# 0.net
KiCad netlist of a schematic drawn in Altium Designer
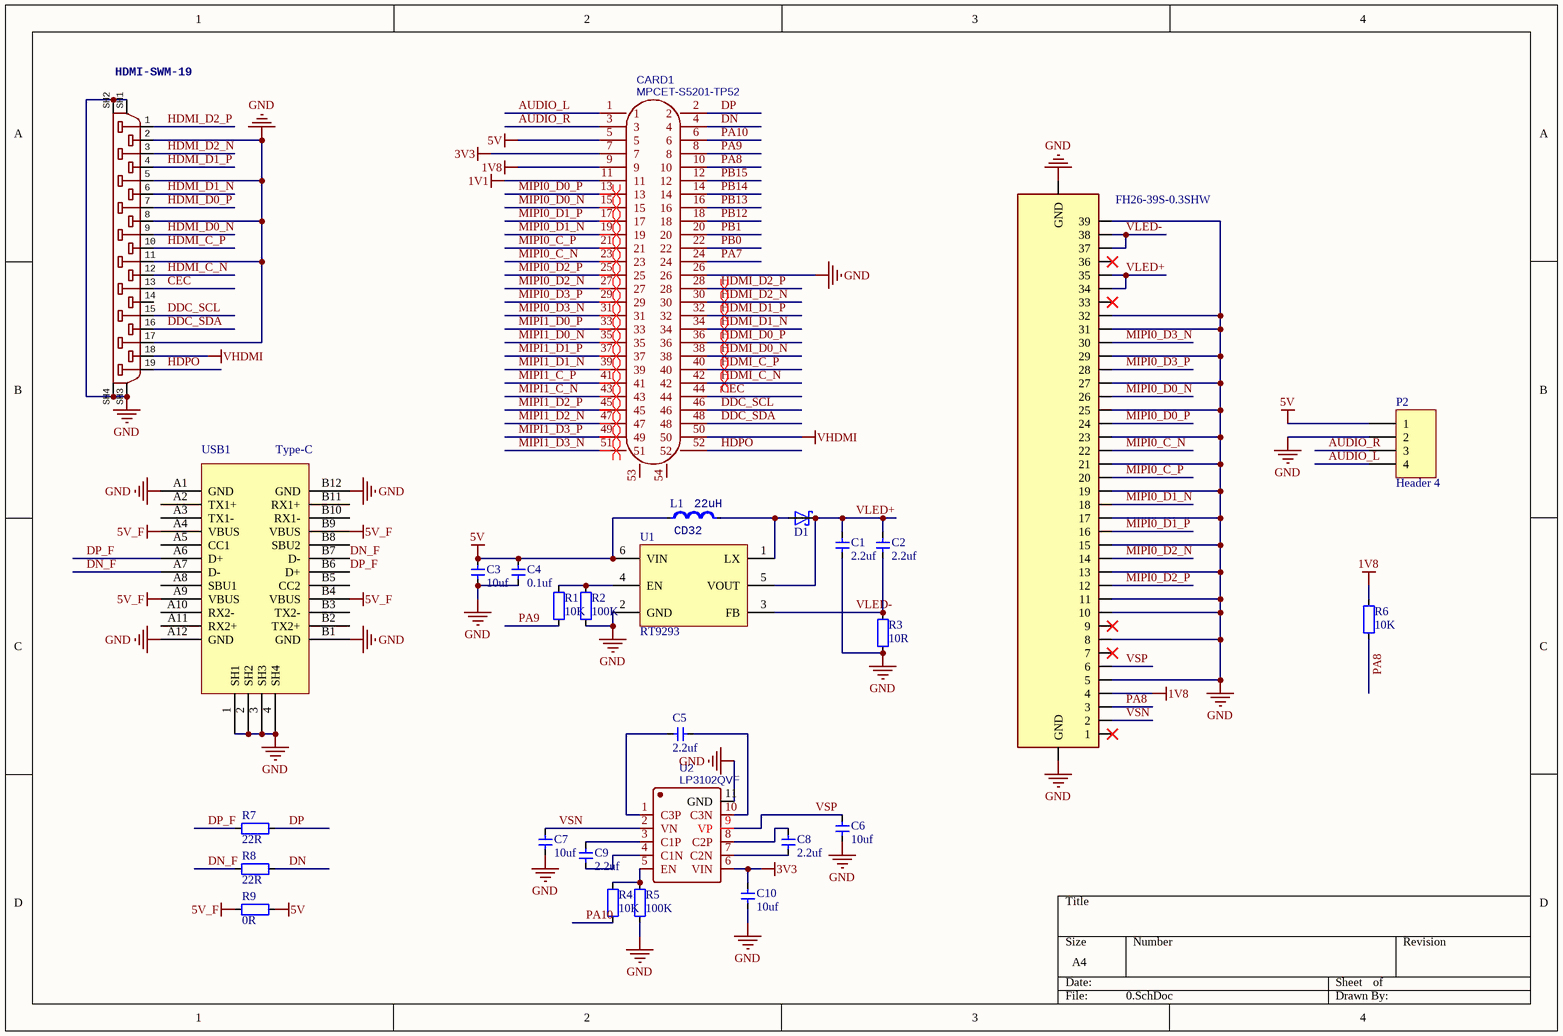
[diagram p0: 0.SchDoc]

(export (version "E")
  (design (tool "Eeschema 10.0.6"))
  (components
    (comp (ref "1")
      (value "FH26-39S-0.3SHW")
      (footprint "FH26-39S-0.3SHW")
      (description "39 Position FPC Connector Contacts, Bottom 0.012 _0.30mm_ Surface Mount, Right Angle")
      (fields (field (name "MF") "Hirose"))
      (libsource (lib "mLib") (part "FH26-39S-0.3SHW"))
    )
    (comp (ref "C1")
      (value "2.2uf")
      (footprint "0603_CAP")
      (description "Capacitor")
      (libsource (lib "MyPcbLib") (part "电容-0402"))
    )
    (comp (ref "C2")
      (value "2.2uf")
      (footprint "0603_CAP")
      (description "Capacitor")
      (libsource (lib "MyPcbLib") (part "电容-0402"))
    )
    (comp (ref "C3")
      (value "10uf")
      (footprint "0603_CAP")
      (description "Capacitor")
      (libsource (lib "MyPcbLib") (part "电容-0402"))
    )
    (comp (ref "C4")
      (value "0.1uf")
      (footprint "0603_CAP")
      (description "Capacitor")
      (libsource (lib "MyPcbLib") (part "电容-0402"))
    )
    (comp (ref "C5")
      (value "2.2uf")
      (footprint "0603_CAP")
      (description "Capacitor")
      (libsource (lib "MyPcbLib") (part "电容-0402"))
    )
    (comp (ref "C6")
      (value "10uf")
      (footprint "0603_CAP")
      (description "Capacitor")
      (libsource (lib "MyPcbLib") (part "电容-0402"))
    )
    (comp (ref "C7")
      (value "10uf")
      (footprint "0603_CAP")
      (description "Capacitor")
      (libsource (lib "MyPcbLib") (part "电容-0402"))
    )
    (comp (ref "C8")
      (value "2.2uf")
      (footprint "0603_CAP")
      (description "Capacitor")
      (libsource (lib "MyPcbLib") (part "电容-0402"))
    )
    (comp (ref "C9")
      (value "2.2uf")
      (footprint "0603_CAP")
      (description "Capacitor")
      (libsource (lib "MyPcbLib") (part "电容-0402"))
    )
    (comp (ref "C10")
      (value "10uf")
      (footprint "0603_CAP")
      (description "Capacitor")
      (libsource (lib "MyPcbLib") (part "电容-0402"))
    )
    (comp (ref "CARD1")
      (value "MPCET-S5201-TP52")
      (footprint "MINI-PCIE-SMD_MPCET-S5201-TP40")
      (fields (field (name "BOM_SUPPLIER PART") "C367018") (field (name "CONTRIBUTOR") "LCSC"))
      (libsource (lib "altium-import") (part "root_0_MPCET-S5201-TP52_"))
    )
    (comp (ref "D1")
      (value "RSX501L-20")
      (footprint "SOD-123F_L2.8-W1.8-LS3.7-RD")
      (description "Diode Schottky 40V 1A Surface Mount SMA _DO-214AC_")
      (fields (field (name "MP") "SS14") (field (name "MF") "ON Semiconductor"))
      (libsource (lib "mLib") (part "RSX501L-20"))
    )
    (comp (ref "HDMI")
      (value "HDMI-SWM-19")
      (footprint "HDMI-SWM-19")
      (libsource (lib "mLib") (part "HDMI-MC34931HDMI-SWM-19"))
    )
    (comp (ref "L1")
      (value "22uH")
      (footprint "IND_CD32")
      (description "Inductor")
      (fields (field (name "TYPE") "CD32") (field (name "Comment") "CD32"))
      (libsource (lib "KitSprout") (part "Ind_CD32"))
    )
    (comp (ref "P2")
      (value "Header 4")
      (footprint "HDR1X4")
      (description "Header, 4-Pin")
      (fields (field (name "PUBLISHER") "Altium Limited"))
      (libsource (lib "Miscellaneous Connectors") (part "Header 4"))
    )
    (comp (ref "R1")
      (value "10K")
      (footprint "0603_RES")
      (description "Resistor")
      (libsource (lib "MyPcbLib") (part "电阻-0402"))
    )
    (comp (ref "R2")
      (value "100K")
      (footprint "0603_RES")
      (description "Resistor")
      (libsource (lib "MyPcbLib") (part "电阻-0402"))
    )
    (comp (ref "R3")
      (value "10R")
      (footprint "0603_RES")
      (description "Resistor")
      (libsource (lib "MyPcbLib") (part "电阻-0402"))
    )
    (comp (ref "R4")
      (value "10K")
      (footprint "0603_RES")
      (description "Resistor")
      (libsource (lib "MyPcbLib") (part "电阻-0402"))
    )
    (comp (ref "R5")
      (value "100K")
      (footprint "0603_RES")
      (description "Resistor")
      (libsource (lib "MyPcbLib") (part "电阻-0402"))
    )
    (comp (ref "R6")
      (value "10K")
      (footprint "0603_RES")
      (description "Resistor")
      (libsource (lib "MyPcbLib") (part "电阻-0402"))
    )
    (comp (ref "R7")
      (value "22R")
      (footprint "0603_RES")
      (description "Resistor")
      (libsource (lib "") (part "电阻-0402_1"))
    )
    (comp (ref "R8")
      (value "22R")
      (footprint "0603_RES")
      (description "Resistor")
      (libsource (lib "") (part "电阻-0402_1"))
    )
    (comp (ref "R9")
      (value "0R")
      (footprint "0603_RES")
      (description "Resistor")
      (libsource (lib "") (part "电阻-0402_1"))
    )
    (comp (ref "U1")
      (value "RT9293")
      (footprint "SOT23-6")
      (description "LCD-LED Driver")
      (libsource (lib "mLib") (part "RT9293"))
    )
    (comp (ref "U2")
      (value "LP3102QVF")
      (footprint "TDFN-10_L3.0-W3.0-P0.50-BL-EP")
      (fields (field (name "BOM_SUPPLIER PART") "C517005") (field (name "CONTRIBUTOR") "LCSC"))
      (libsource (lib "altium-import") (part "root_0_LP3102QVF_"))
    )
    (comp (ref "USB1")
      (value "Type-C")
      (footprint "Type-C-TOP")
      (libsource (lib "MyPcbLib") (part "USB-Type-C-TOP"))
    )
  )
  (nets
    (net (code "1") (name "/AUDIO_L") (class "Default")
      (node (ref "CARD1") (pin "1") (pinfunction "1_1") (pintype "passive"))
      (node (ref "P2") (pin "4") (pinfunction "4_4") (pintype "passive"))
    )
    (net (code "2") (name "/AUDIO_R") (class "Default")
      (node (ref "CARD1") (pin "3") (pinfunction "3_3") (pintype "passive"))
      (node (ref "P2") (pin "3") (pinfunction "3_3") (pintype "passive"))
    )
    (net (code "3") (name "/CEC") (class "Default")
      (node (ref "CARD1") (pin "44") (pinfunction "44_44") (pintype "passive"))
      (node (ref "HDMI") (pin "13") (pinfunction "13_13") (pintype "passive"))
    )
    (net (code "4") (name "/DDC_SCL") (class "Default")
      (node (ref "CARD1") (pin "46") (pinfunction "46_46") (pintype "passive"))
      (node (ref "HDMI") (pin "15") (pinfunction "15_15") (pintype "passive"))
    )
    (net (code "5") (name "/DDC_SDA") (class "Default")
      (node (ref "CARD1") (pin "48") (pinfunction "48_48") (pintype "passive"))
      (node (ref "HDMI") (pin "16") (pinfunction "16_16") (pintype "passive"))
    )
    (net (code "6") (name "/DN") (class "Default")
      (node (ref "CARD1") (pin "4") (pinfunction "4_4") (pintype "passive"))
      (node (ref "R8") (pin "2") (pinfunction "2_2") (pintype "passive"))
    )
    (net (code "7") (name "/DN_F") (class "Default")
      (node (ref "R8") (pin "1") (pinfunction "1_1") (pintype "passive"))
      (node (ref "USB1") (pin "A7") (pinfunction "D-_A7") (pintype "passive"))
      (node (ref "USB1") (pin "B7") (pinfunction "D-_B7") (pintype "passive"))
    )
    (net (code "8") (name "/DP") (class "Default")
      (node (ref "CARD1") (pin "2") (pinfunction "2_2") (pintype "passive"))
      (node (ref "R7") (pin "2") (pinfunction "2_2") (pintype "passive"))
    )
    (net (code "9") (name "/DP_F") (class "Default")
      (node (ref "R7") (pin "1") (pinfunction "1_1") (pintype "passive"))
      (node (ref "USB1") (pin "A6") (pinfunction "D+_A6") (pintype "passive"))
      (node (ref "USB1") (pin "B6") (pinfunction "D+_B6") (pintype "passive"))
    )
    (net (code "10") (name "/HDMI_C_N") (class "Default")
      (node (ref "CARD1") (pin "42") (pinfunction "42_42") (pintype "passive"))
      (node (ref "HDMI") (pin "12") (pinfunction "12_12") (pintype "passive"))
    )
    (net (code "11") (name "/HDMI_C_P") (class "Default")
      (node (ref "CARD1") (pin "40") (pinfunction "40_40") (pintype "passive"))
      (node (ref "HDMI") (pin "10") (pinfunction "10_10") (pintype "passive"))
    )
    (net (code "12") (name "/HDMI_D0_N") (class "Default")
      (node (ref "CARD1") (pin "38") (pinfunction "38_38") (pintype "passive"))
      (node (ref "HDMI") (pin "9") (pinfunction "9_9") (pintype "passive"))
    )
    (net (code "13") (name "/HDMI_D0_P") (class "Default")
      (node (ref "CARD1") (pin "36") (pinfunction "36_36") (pintype "passive"))
      (node (ref "HDMI") (pin "7") (pinfunction "7_7") (pintype "passive"))
    )
    (net (code "14") (name "/HDMI_D1_N") (class "Default")
      (node (ref "CARD1") (pin "34") (pinfunction "34_34") (pintype "passive"))
      (node (ref "HDMI") (pin "6") (pinfunction "6_6") (pintype "passive"))
    )
    (net (code "15") (name "/HDMI_D1_P") (class "Default")
      (node (ref "CARD1") (pin "32") (pinfunction "32_32") (pintype "passive"))
      (node (ref "HDMI") (pin "4") (pinfunction "4_4") (pintype "passive"))
    )
    (net (code "16") (name "/HDMI_D2_N") (class "Default")
      (node (ref "CARD1") (pin "30") (pinfunction "30_30") (pintype "passive"))
      (node (ref "HDMI") (pin "3") (pinfunction "3_3") (pintype "passive"))
    )
    (net (code "17") (name "/HDMI_D2_P") (class "Default")
      (node (ref "CARD1") (pin "28") (pinfunction "28_28") (pintype "passive"))
      (node (ref "HDMI") (pin "1") (pinfunction "1_1") (pintype "passive"))
    )
    (net (code "18") (name "/HDPO") (class "Default")
      (node (ref "CARD1") (pin "52") (pinfunction "52_52") (pintype "passive"))
      (node (ref "HDMI") (pin "19") (pinfunction "19_19") (pintype "passive"))
    )
    (net (code "19") (name "/MIPI0_C_N") (class "Default")
      (node (ref "1") (pin "22") (pinfunction "22_22") (pintype "bidirectional"))
      (node (ref "CARD1") (pin "23") (pinfunction "23_23") (pintype "passive"))
    )
    (net (code "20") (name "/MIPI0_C_P") (class "Default")
      (node (ref "1") (pin "20") (pinfunction "20_20") (pintype "bidirectional"))
      (node (ref "CARD1") (pin "21") (pinfunction "21_21") (pintype "passive"))
    )
    (net (code "21") (name "/MIPI0_D0_N") (class "Default")
      (node (ref "1") (pin "26") (pinfunction "26_26") (pintype "bidirectional"))
      (node (ref "CARD1") (pin "15") (pinfunction "15_15") (pintype "passive"))
    )
    (net (code "22") (name "/MIPI0_D0_P") (class "Default")
      (node (ref "1") (pin "24") (pinfunction "24_24") (pintype "bidirectional"))
      (node (ref "CARD1") (pin "13") (pinfunction "13_13") (pintype "passive"))
    )
    (net (code "23") (name "/MIPI0_D1_N") (class "Default")
      (node (ref "1") (pin "18") (pinfunction "18_18") (pintype "bidirectional"))
      (node (ref "CARD1") (pin "19") (pinfunction "19_19") (pintype "passive"))
    )
    (net (code "24") (name "/MIPI0_D1_P") (class "Default")
      (node (ref "1") (pin "16") (pinfunction "16_16") (pintype "bidirectional"))
      (node (ref "CARD1") (pin "17") (pinfunction "17_17") (pintype "passive"))
    )
    (net (code "25") (name "/MIPI0_D2_N") (class "Default")
      (node (ref "1") (pin "14") (pinfunction "14_14") (pintype "bidirectional"))
      (node (ref "CARD1") (pin "27") (pinfunction "27_27") (pintype "passive"))
    )
    (net (code "26") (name "/MIPI0_D2_P") (class "Default")
      (node (ref "1") (pin "12") (pinfunction "12_12") (pintype "bidirectional"))
      (node (ref "CARD1") (pin "25") (pinfunction "25_25") (pintype "passive"))
    )
    (net (code "27") (name "/MIPI0_D3_N") (class "Default")
      (node (ref "1") (pin "30") (pinfunction "30_30") (pintype "bidirectional"))
      (node (ref "CARD1") (pin "31") (pinfunction "31_31") (pintype "passive"))
    )
    (net (code "28") (name "/MIPI0_D3_P") (class "Default")
      (node (ref "1") (pin "28") (pinfunction "28_28") (pintype "bidirectional"))
      (node (ref "CARD1") (pin "29") (pinfunction "29_29") (pintype "passive"))
    )
    (net (code "29") (name "/MIPI1_C_N") (class "Default")
      (node (ref "CARD1") (pin "43") (pinfunction "43_43") (pintype "passive"))
    )
    (net (code "30") (name "/MIPI1_C_P") (class "Default")
      (node (ref "CARD1") (pin "41") (pinfunction "41_41") (pintype "passive"))
    )
    (net (code "31") (name "/MIPI1_D0_N") (class "Default")
      (node (ref "CARD1") (pin "35") (pinfunction "35_35") (pintype "passive"))
    )
    (net (code "32") (name "/MIPI1_D0_P") (class "Default")
      (node (ref "CARD1") (pin "33") (pinfunction "33_33") (pintype "passive"))
    )
    (net (code "33") (name "/MIPI1_D1_N") (class "Default")
      (node (ref "CARD1") (pin "39") (pinfunction "39_39") (pintype "passive"))
    )
    (net (code "34") (name "/MIPI1_D1_P") (class "Default")
      (node (ref "CARD1") (pin "37") (pinfunction "37_37") (pintype "passive"))
    )
    (net (code "35") (name "/MIPI1_D2_N") (class "Default")
      (node (ref "CARD1") (pin "47") (pinfunction "47_47") (pintype "passive"))
    )
    (net (code "36") (name "/MIPI1_D2_P") (class "Default")
      (node (ref "CARD1") (pin "45") (pinfunction "45_45") (pintype "passive"))
    )
    (net (code "37") (name "/MIPI1_D3_N") (class "Default")
      (node (ref "CARD1") (pin "51") (pinfunction "51_51") (pintype "passive"))
    )
    (net (code "38") (name "/MIPI1_D3_P") (class "Default")
      (node (ref "CARD1") (pin "49") (pinfunction "49_49") (pintype "passive"))
    )
    (net (code "39") (name "/PA7") (class "Default")
      (node (ref "CARD1") (pin "24") (pinfunction "24_24") (pintype "passive"))
    )
    (net (code "40") (name "/PA8") (class "Default")
      (node (ref "1") (pin "3") (pinfunction "3_3") (pintype "bidirectional"))
      (node (ref "CARD1") (pin "10") (pinfunction "10_10") (pintype "passive"))
      (node (ref "R6") (pin "2") (pinfunction "2_2") (pintype "passive"))
    )
    (net (code "41") (name "/PA9") (class "Default")
      (node (ref "CARD1") (pin "8") (pinfunction "8_8") (pintype "passive"))
      (node (ref "R1") (pin "2") (pinfunction "2_2") (pintype "passive"))
    )
    (net (code "42") (name "/PA10") (class "Default")
      (node (ref "CARD1") (pin "6") (pinfunction "6_6") (pintype "passive"))
      (node (ref "R4") (pin "2") (pinfunction "2_2") (pintype "passive"))
    )
    (net (code "43") (name "/PB0") (class "Default")
      (node (ref "CARD1") (pin "22") (pinfunction "22_22") (pintype "passive"))
    )
    (net (code "44") (name "/PB1") (class "Default")
      (node (ref "CARD1") (pin "20") (pinfunction "20_20") (pintype "passive"))
    )
    (net (code "45") (name "/PB12") (class "Default")
      (node (ref "CARD1") (pin "18") (pinfunction "18_18") (pintype "passive"))
    )
    (net (code "46") (name "/PB13") (class "Default")
      (node (ref "CARD1") (pin "16") (pinfunction "16_16") (pintype "passive"))
    )
    (net (code "47") (name "/PB14") (class "Default")
      (node (ref "CARD1") (pin "14") (pinfunction "14_14") (pintype "passive"))
    )
    (net (code "48") (name "/PB15") (class "Default")
      (node (ref "CARD1") (pin "12") (pinfunction "12_12") (pintype "passive"))
    )
    (net (code "49") (name "/VLED+") (class "Default")
      (node (ref "1") (pin "34") (pinfunction "34_34") (pintype "bidirectional"))
      (node (ref "1") (pin "35") (pinfunction "35_35") (pintype "bidirectional"))
      (node (ref "C1") (pin "2") (pinfunction "2_2") (pintype "passive"))
      (node (ref "C2") (pin "2") (pinfunction "2_2") (pintype "passive"))
      (node (ref "D1") (pin "1") (pinfunction "1_1") (pintype "passive"))
      (node (ref "U1") (pin "5") (pinfunction "VOUT_5") (pintype "passive"))
    )
    (net (code "50") (name "/VLED-") (class "Default")
      (node (ref "1") (pin "37") (pinfunction "37_37") (pintype "bidirectional"))
      (node (ref "1") (pin "38") (pinfunction "38_38") (pintype "bidirectional"))
      (node (ref "C2") (pin "1") (pinfunction "1_1") (pintype "passive"))
      (node (ref "R3") (pin "1") (pinfunction "1_1") (pintype "passive"))
      (node (ref "U1") (pin "3") (pinfunction "FB_3") (pintype "passive"))
    )
    (net (code "51") (name "/VSN") (class "Default")
      (node (ref "1") (pin "2") (pinfunction "2_2") (pintype "bidirectional"))
      (node (ref "C7") (pin "2") (pinfunction "2_2") (pintype "passive"))
      (node (ref "U2") (pin "2") (pinfunction "VN_2") (pintype "passive"))
    )
    (net (code "52") (name "/VSP") (class "Default")
      (node (ref "1") (pin "6") (pinfunction "6_6") (pintype "bidirectional"))
      (node (ref "C6") (pin "2") (pinfunction "2_2") (pintype "passive"))
      (node (ref "U2") (pin "9") (pinfunction "VP_9") (pintype "passive"))
    )
    (net (code "53") (name "1V1") (class "Default")
      (node (ref "CARD1") (pin "11") (pinfunction "11_11") (pintype "passive"))
    )
    (net (code "54") (name "1V8") (class "Default")
      (node (ref "1") (pin "4") (pinfunction "4_4") (pintype "bidirectional"))
      (node (ref "CARD1") (pin "9") (pinfunction "9_9") (pintype "passive"))
      (node (ref "R6") (pin "1") (pinfunction "1_1") (pintype "passive"))
    )
    (net (code "55") (name "3V3") (class "Default")
      (node (ref "C10") (pin "2") (pinfunction "2_2") (pintype "passive"))
      (node (ref "CARD1") (pin "7") (pinfunction "7_7") (pintype "passive"))
      (node (ref "U2") (pin "6") (pinfunction "VIN_6") (pintype "passive"))
    )
    (net (code "56") (name "5V") (class "Default")
      (node (ref "C3") (pin "2") (pinfunction "2_2") (pintype "passive"))
      (node (ref "C4") (pin "2") (pinfunction "2_2") (pintype "passive"))
      (node (ref "CARD1") (pin "5") (pinfunction "5_5") (pintype "passive"))
      (node (ref "L1") (pin "1") (pinfunction "1_1") (pintype "passive"))
      (node (ref "P2") (pin "1") (pinfunction "1_1") (pintype "passive"))
      (node (ref "R9") (pin "2") (pinfunction "2_2") (pintype "passive"))
      (node (ref "U1") (pin "6") (pinfunction "VIN_6") (pintype "passive"))
    )
    (net (code "57") (name "5V_F") (class "Default")
      (node (ref "R9") (pin "1") (pinfunction "1_1") (pintype "passive"))
      (node (ref "USB1") (pin "A4") (pinfunction "VBUS_A4") (pintype "passive"))
      (node (ref "USB1") (pin "A9") (pinfunction "VBUS_A9") (pintype "passive"))
      (node (ref "USB1") (pin "B4") (pinfunction "VBUS_B4") (pintype "passive"))
      (node (ref "USB1") (pin "B9") (pinfunction "VBUS_B9") (pintype "passive"))
    )
    (net (code "58") (name "GND") (class "Default")
      (node (ref "1") (pin "10") (pinfunction "10_10") (pintype "bidirectional"))
      (node (ref "1") (pin "11") (pinfunction "11_11") (pintype "bidirectional"))
      (node (ref "1") (pin "13") (pinfunction "13_13") (pintype "bidirectional"))
      (node (ref "1") (pin "15") (pinfunction "15_15") (pintype "bidirectional"))
      (node (ref "1") (pin "17") (pinfunction "17_17") (pintype "bidirectional"))
      (node (ref "1") (pin "19") (pinfunction "19_19") (pintype "bidirectional"))
      (node (ref "1") (pin "21") (pinfunction "21_21") (pintype "bidirectional"))
      (node (ref "1") (pin "23") (pinfunction "23_23") (pintype "bidirectional"))
      (node (ref "1") (pin "25") (pinfunction "25_25") (pintype "bidirectional"))
      (node (ref "1") (pin "27") (pinfunction "27_27") (pintype "bidirectional"))
      (node (ref "1") (pin "29") (pinfunction "29_29") (pintype "bidirectional"))
      (node (ref "1") (pin "31") (pinfunction "31_31") (pintype "bidirectional"))
      (node (ref "1") (pin "32") (pinfunction "32_32") (pintype "bidirectional"))
      (node (ref "1") (pin "39") (pinfunction "39_39") (pintype "bidirectional"))
      (node (ref "1") (pin "5") (pinfunction "5_5") (pintype "bidirectional"))
      (node (ref "1") (pin "8") (pinfunction "8_8") (pintype "bidirectional"))
      (node (ref "1") (pin "GND1") (pinfunction "GND_GND1") (pintype "power_in"))
      (node (ref "1") (pin "GND2") (pinfunction "GND_GND2") (pintype "power_in"))
      (node (ref "C1") (pin "1") (pinfunction "1_1") (pintype "passive"))
      (node (ref "C10") (pin "1") (pinfunction "1_1") (pintype "passive"))
      (node (ref "C3") (pin "1") (pinfunction "1_1") (pintype "passive"))
      (node (ref "C4") (pin "1") (pinfunction "1_1") (pintype "passive"))
      (node (ref "C6") (pin "1") (pinfunction "1_1") (pintype "passive"))
      (node (ref "C7") (pin "1") (pinfunction "1_1") (pintype "passive"))
      (node (ref "CARD1") (pin "26") (pinfunction "26_26") (pintype "passive"))
      (node (ref "HDMI") (pin "11") (pinfunction "11_11") (pintype "passive"))
      (node (ref "HDMI") (pin "17") (pinfunction "17_17") (pintype "passive"))
      (node (ref "HDMI") (pin "2") (pinfunction "2_2") (pintype "passive"))
      (node (ref "HDMI") (pin "5") (pinfunction "5_5") (pintype "passive"))
      (node (ref "HDMI") (pin "8") (pinfunction "8_8") (pintype "passive"))
      (node (ref "HDMI") (pin "SH1") (pinfunction "20_SH1") (pintype "passive"))
      (node (ref "HDMI") (pin "SH2") (pinfunction "21_SH2") (pintype "passive"))
      (node (ref "HDMI") (pin "SH3") (pinfunction "22_SH3") (pintype "passive"))
      (node (ref "HDMI") (pin "SH4") (pinfunction "23_SH4") (pintype "passive"))
      (node (ref "P2") (pin "2") (pinfunction "2_2") (pintype "passive"))
      (node (ref "R2") (pin "2") (pinfunction "2_2") (pintype "passive"))
      (node (ref "R3") (pin "2") (pinfunction "2_2") (pintype "passive"))
      (node (ref "R5") (pin "2") (pinfunction "2_2") (pintype "passive"))
      (node (ref "U1") (pin "2") (pinfunction "GND_2") (pintype "passive"))
      (node (ref "U2") (pin "11") (pinfunction "GND_11") (pintype "passive"))
      (node (ref "USB1") (pin "1") (pinfunction "SH1_1") (pintype "passive"))
      (node (ref "USB1") (pin "2") (pinfunction "SH2_2") (pintype "passive"))
      (node (ref "USB1") (pin "3") (pinfunction "SH3_3") (pintype "passive"))
      (node (ref "USB1") (pin "4") (pinfunction "SH4_4") (pintype "passive"))
      (node (ref "USB1") (pin "A1") (pinfunction "GND_A1") (pintype "passive"))
      (node (ref "USB1") (pin "A12") (pinfunction "GND_A12") (pintype "passive"))
      (node (ref "USB1") (pin "B1") (pinfunction "GND_B1") (pintype "passive"))
      (node (ref "USB1") (pin "B12") (pinfunction "GND_B12") (pintype "passive"))
    )
    (net (code "59") (name "Net-(U1-EN)") (class "Default")
      (node (ref "R1") (pin "1") (pinfunction "1_1") (pintype "passive"))
      (node (ref "R2") (pin "1") (pinfunction "1_1") (pintype "passive"))
      (node (ref "U1") (pin "4") (pinfunction "EN_4") (pintype "passive"))
    )
    (net (code "60") (name "Net-(U1-LX)") (class "Default")
      (node (ref "D1") (pin "2") (pinfunction "2_2") (pintype "passive"))
      (node (ref "L1") (pin "2") (pinfunction "2_2") (pintype "passive"))
      (node (ref "U1") (pin "1") (pinfunction "LX_1") (pintype "passive"))
    )
    (net (code "61") (name "Net-(U2-C1N)") (class "Default")
      (node (ref "C9") (pin "2") (pinfunction "2_2") (pintype "passive"))
      (node (ref "U2") (pin "4") (pinfunction "C1N_4") (pintype "passive"))
    )
    (net (code "62") (name "Net-(U2-C1P)") (class "Default")
      (node (ref "C9") (pin "1") (pinfunction "1_1") (pintype "passive"))
      (node (ref "U2") (pin "3") (pinfunction "C1P_3") (pintype "passive"))
    )
    (net (code "63") (name "Net-(U2-C2N)") (class "Default")
      (node (ref "C8") (pin "2") (pinfunction "2_2") (pintype "passive"))
      (node (ref "U2") (pin "7") (pinfunction "C2N_7") (pintype "passive"))
    )
    (net (code "64") (name "Net-(U2-C2P)") (class "Default")
      (node (ref "C8") (pin "1") (pinfunction "1_1") (pintype "passive"))
      (node (ref "U2") (pin "8") (pinfunction "C2P_8") (pintype "passive"))
    )
    (net (code "65") (name "Net-(U2-C3N)") (class "Default")
      (node (ref "C5") (pin "1") (pinfunction "1_1") (pintype "passive"))
      (node (ref "U2") (pin "10") (pinfunction "C3N_10") (pintype "passive"))
    )
    (net (code "66") (name "Net-(U2-C3P)") (class "Default")
      (node (ref "C5") (pin "2") (pinfunction "2_2") (pintype "passive"))
      (node (ref "U2") (pin "1") (pinfunction "C3P_1") (pintype "passive"))
    )
    (net (code "67") (name "Net-(U2-EN)") (class "Default")
      (node (ref "R4") (pin "1") (pinfunction "1_1") (pintype "passive"))
      (node (ref "R5") (pin "1") (pinfunction "1_1") (pintype "passive"))
      (node (ref "U2") (pin "5") (pinfunction "EN_5") (pintype "passive"))
    )
    (net (code "68") (name "VHDMI") (class "Default")
      (node (ref "CARD1") (pin "50") (pinfunction "50_50") (pintype "passive"))
      (node (ref "HDMI") (pin "18") (pinfunction "18_18") (pintype "passive"))
    )
    (net (code "69") (name "unconnected-(1-Pad1)") (class "Default")
      (node (ref "1") (pin "1") (pinfunction "1_1") (pintype "bidirectional+no_connect"))
    )
    (net (code "70") (name "unconnected-(1-Pad7)") (class "Default")
      (node (ref "1") (pin "7") (pinfunction "7_7") (pintype "bidirectional+no_connect"))
    )
    (net (code "71") (name "unconnected-(1-Pad9)") (class "Default")
      (node (ref "1") (pin "9") (pinfunction "9_9") (pintype "bidirectional+no_connect"))
    )
    (net (code "72") (name "unconnected-(1-Pad33)") (class "Default")
      (node (ref "1") (pin "33") (pinfunction "33_33") (pintype "bidirectional+no_connect"))
    )
    (net (code "73") (name "unconnected-(1-Pad36)") (class "Default")
      (node (ref "1") (pin "36") (pinfunction "36_36") (pintype "bidirectional+no_connect"))
    )
    (net (code "74") (name "unconnected-(CARD1-Pad53)") (class "Default")
      (node (ref "CARD1") (pin "53") (pinfunction "53_53") (pintype "passive"))
    )
    (net (code "75") (name "unconnected-(CARD1-Pad54)") (class "Default")
      (node (ref "CARD1") (pin "54") (pinfunction "54_54") (pintype "passive"))
    )
    (net (code "76") (name "unconnected-(HDMI-Pad14)") (class "Default")
      (node (ref "HDMI") (pin "14") (pinfunction "14_14") (pintype "passive"))
    )
    (net (code "77") (name "unconnected-(USB1-CC1-PadA5)") (class "Default")
      (node (ref "USB1") (pin "A5") (pinfunction "CC1_A5") (pintype "passive"))
    )
    (net (code "78") (name "unconnected-(USB1-CC2-PadB5)") (class "Default")
      (node (ref "USB1") (pin "B5") (pinfunction "CC2_B5") (pintype "passive"))
    )
    (net (code "79") (name "unconnected-(USB1-RX1+-PadB11)") (class "Default")
      (node (ref "USB1") (pin "B11") (pinfunction "RX1+_B11") (pintype "passive"))
    )
    (net (code "80") (name "unconnected-(USB1-RX1--PadB10)") (class "Default")
      (node (ref "USB1") (pin "B10") (pinfunction "RX1-_B10") (pintype "passive"))
    )
    (net (code "81") (name "unconnected-(USB1-RX2+-PadA11)") (class "Default")
      (node (ref "USB1") (pin "A11") (pinfunction "RX2+_A11") (pintype "passive"))
    )
    (net (code "82") (name "unconnected-(USB1-RX2--PadA10)") (class "Default")
      (node (ref "USB1") (pin "A10") (pinfunction "RX2-_A10") (pintype "passive"))
    )
    (net (code "83") (name "unconnected-(USB1-SBU1-PadA8)") (class "Default")
      (node (ref "USB1") (pin "A8") (pinfunction "SBU1_A8") (pintype "passive"))
    )
    (net (code "84") (name "unconnected-(USB1-SBU2-PadB8)") (class "Default")
      (node (ref "USB1") (pin "B8") (pinfunction "SBU2_B8") (pintype "passive"))
    )
    (net (code "85") (name "unconnected-(USB1-TX1+-PadA2)") (class "Default")
      (node (ref "USB1") (pin "A2") (pinfunction "TX1+_A2") (pintype "passive"))
    )
    (net (code "86") (name "unconnected-(USB1-TX1--PadA3)") (class "Default")
      (node (ref "USB1") (pin "A3") (pinfunction "TX1-_A3") (pintype "passive"))
    )
    (net (code "87") (name "unconnected-(USB1-TX2+-PadB2)") (class "Default")
      (node (ref "USB1") (pin "B2") (pinfunction "TX2+_B2") (pintype "passive"))
    )
    (net (code "88") (name "unconnected-(USB1-TX2--PadB3)") (class "Default")
      (node (ref "USB1") (pin "B3") (pinfunction "TX2-_B3") (pintype "passive"))
    )
  )
)
